# 2Filters.net
KiCad netlist of a schematic drawn in Altium Designer
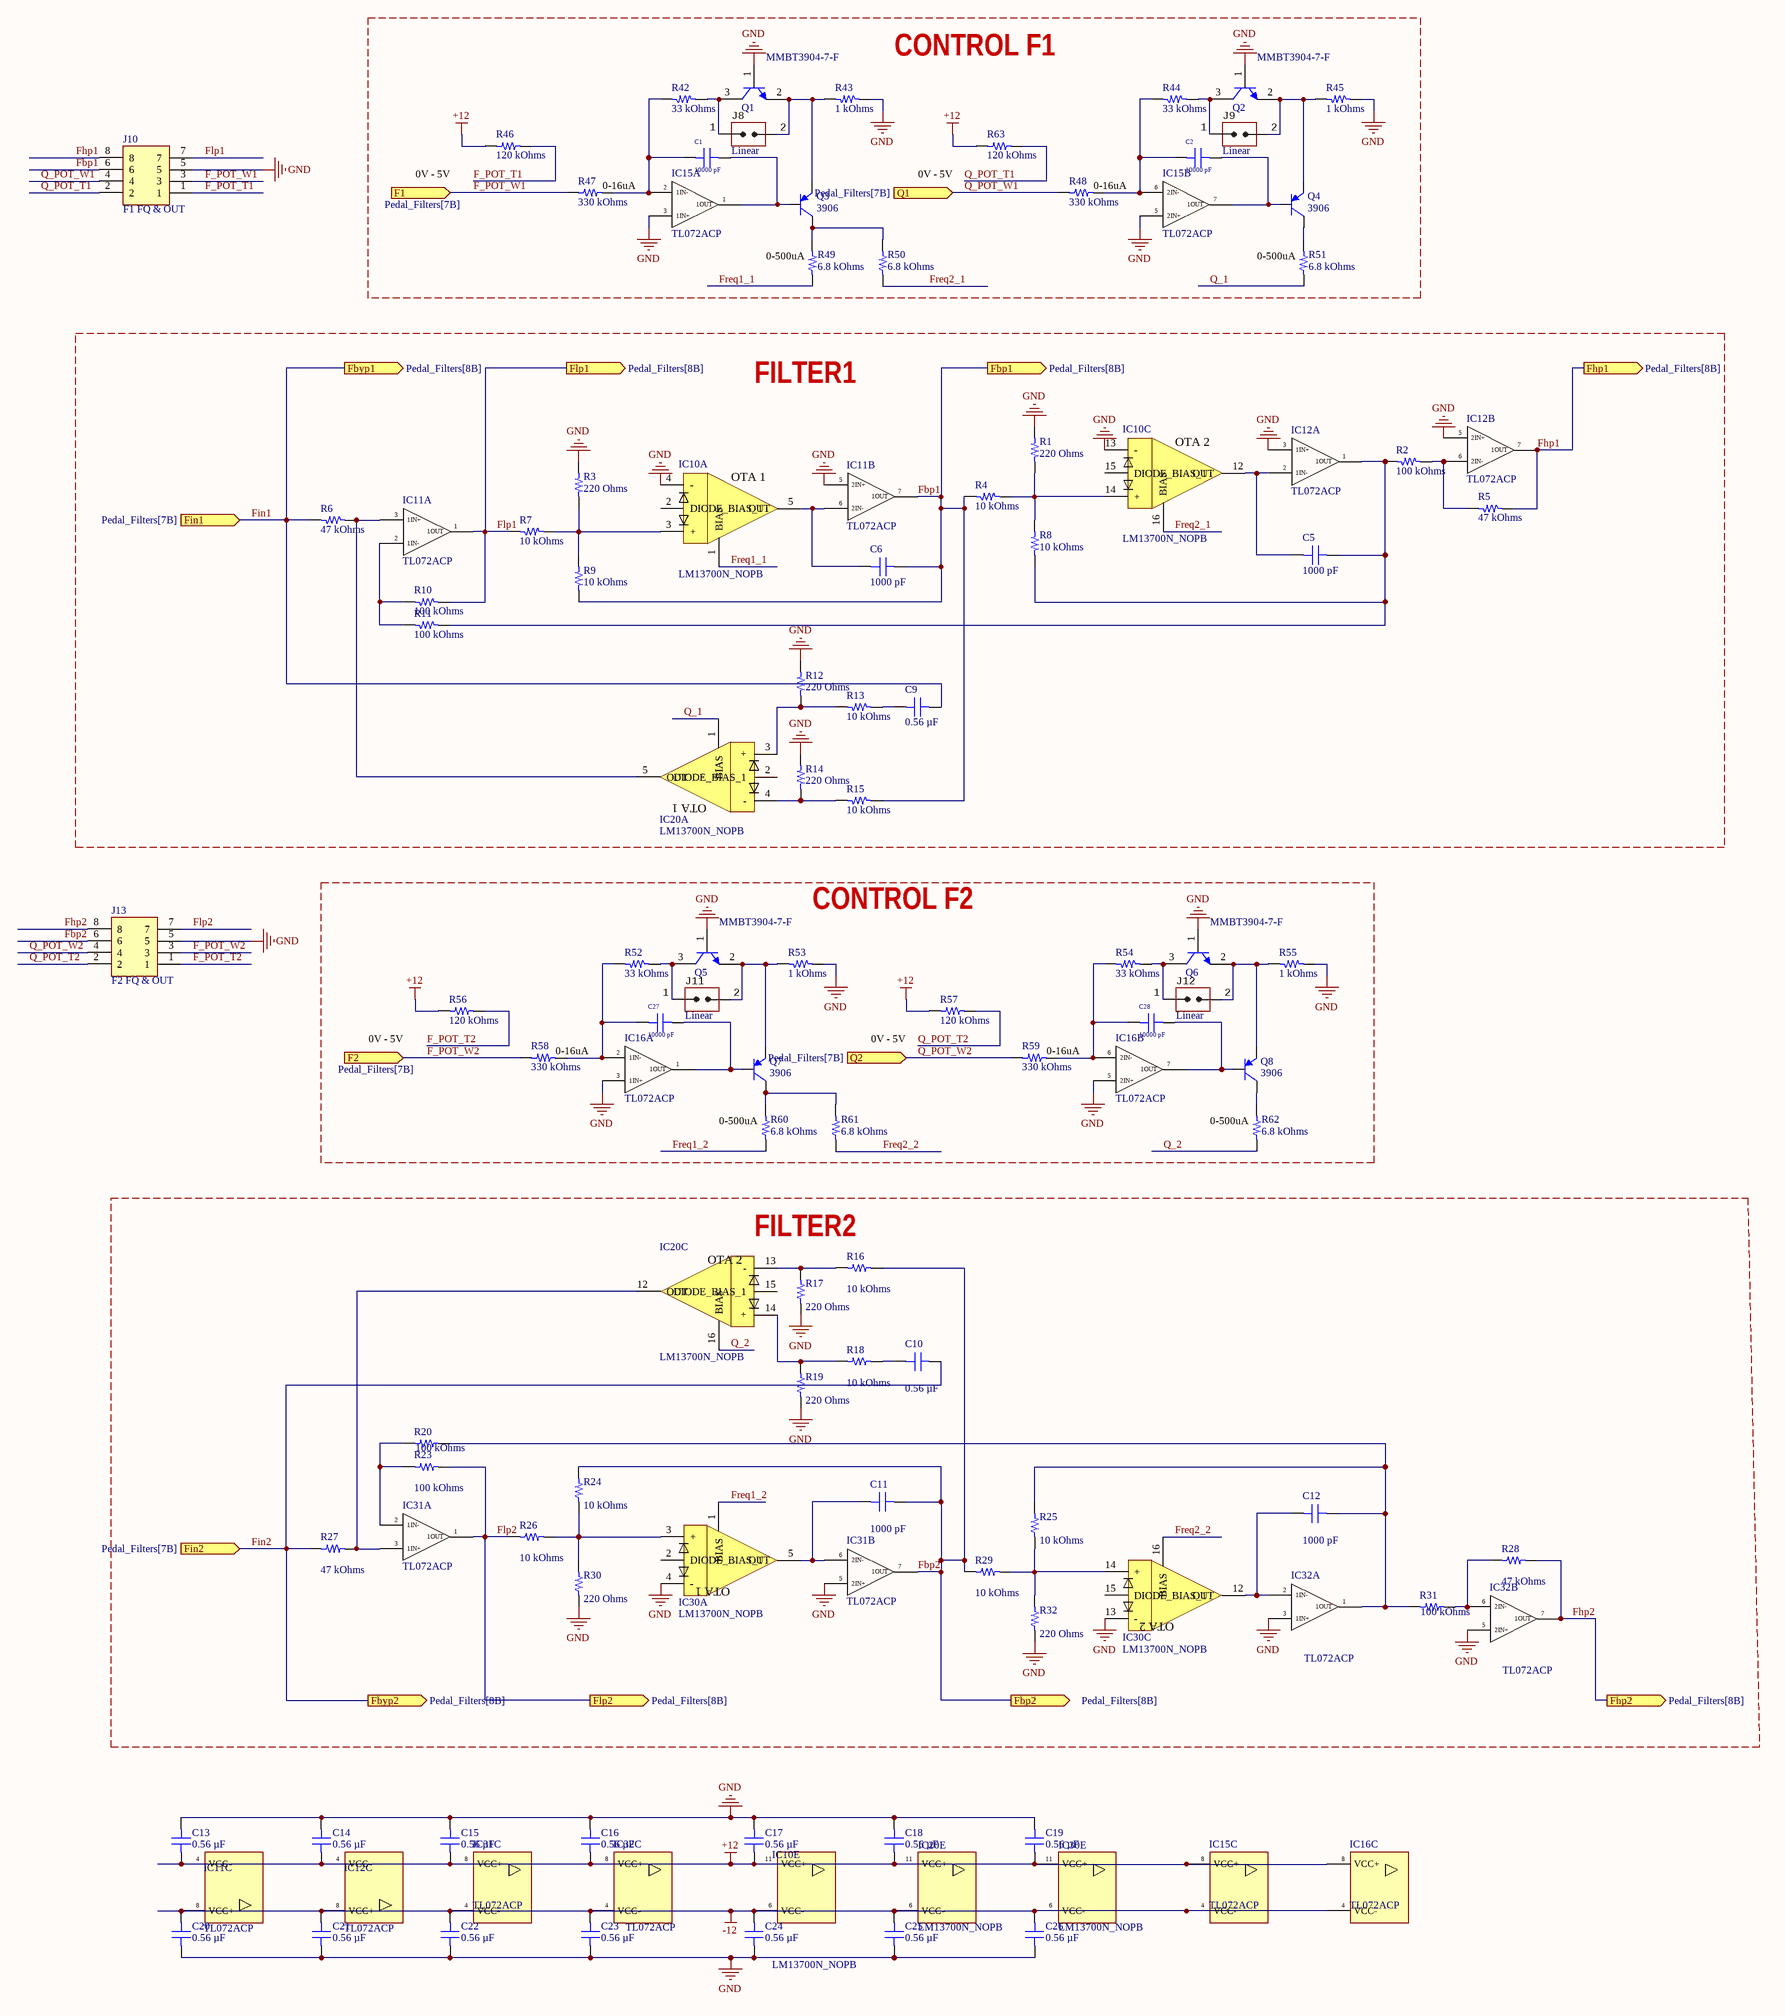
[diagram p0: 2Filters.SchDoc]

(export (version "E")
  (design (tool "Eeschema 10.0.6"))
  (components
    (comp (ref "C1")
      (value "10000 pF")
      (footprint "MURATA GRM188 0603_1608")
      (description "CAP CER 10000PF 50V C0G/NP0 0603")
      (fields
        (field (name "PART NUMBER") "GRM1885C1H103JA01D")
        (field (name "CAPACITANCE") "10000 pF")
        (field (name "MANUFACTURER") "Murata Electronics")
      )
      (libsource (lib "Celestial Altium Library - altium_library") (part "Capacitor"))
    )
    (comp (ref "C2")
      (value "10000 pF")
      (footprint "MURATA GRM188 0603_1608")
      (description "CAP CER 10000PF 50V C0G/NP0 0603")
      (fields
        (field (name "PART NUMBER") "GRM1885C1H103JA01D")
        (field (name "CAPACITANCE") "10000 pF")
        (field (name "MANUFACTURER") "Murata Electronics")
      )
      (libsource (lib "Celestial Altium Library - altium_library") (part "Capacitor"))
    )
    (comp (ref "C5")
      (value "~")
      (footprint "CAP 0805_2012")
      (description "CAP CER 0805 1NF 50V ULTRA STABL")
      (fields (field (name "PART NUMBER") "C0805X102J5HACAUTO") (field (name "CAPACITANCE") "1000 pF"))
      (libsource (lib "Celestial Altium Library - altium_library") (part "Capacitor"))
    )
    (comp (ref "C6")
      (value "~")
      (footprint "CAP 0805_2012")
      (description "CAP CER 0805 1NF 50V ULTRA STABL")
      (fields (field (name "PART NUMBER") "C0805X102J5HACAUTO") (field (name "CAPACITANCE") "1000 pF"))
      (libsource (lib "Celestial Altium Library - altium_library") (part "Capacitor"))
    )
    (comp (ref "C9")
      (value "~")
      (footprint "CAP 0805_2012")
      (description "CAP CER 0.56UF 50V X7R 0805")
      (fields (field (name "PART NUMBER") "C0805C564K5RAC7800") (field (name "CAPACITANCE") "0.56 µF"))
      (libsource (lib "Celestial Altium Library - altium_library") (part "Capacitor"))
    )
    (comp (ref "C10")
      (value "~")
      (footprint "CAP 0805_2012")
      (description "CAP CER 0.56UF 50V X7R 0805")
      (fields (field (name "PART NUMBER") "C0805C564K5RAC7800") (field (name "CAPACITANCE") "0.56 µF"))
      (libsource (lib "Celestial Altium Library - altium_library") (part "Capacitor"))
    )
    (comp (ref "C11")
      (value "~")
      (footprint "CAP 0805_2012")
      (description "CAP CER 0805 1NF 50V ULTRA STABL")
      (fields (field (name "PART NUMBER") "C0805X102J5HACAUTO") (field (name "CAPACITANCE") "1000 pF"))
      (libsource (lib "Celestial Altium Library - altium_library") (part "Capacitor"))
    )
    (comp (ref "C12")
      (value "~")
      (footprint "CAP 0805_2012")
      (description "CAP CER 0805 1NF 50V ULTRA STABL")
      (fields (field (name "PART NUMBER") "C0805X102J5HACAUTO") (field (name "CAPACITANCE") "1000 pF"))
      (libsource (lib "Celestial Altium Library - altium_library") (part "Capacitor"))
    )
    (comp (ref "C13")
      (value "~")
      (footprint "CAP 0805_2012")
      (description "CAP CER 0.56UF 50V X7R 0805")
      (fields (field (name "PART NUMBER") "C0805C564K5RAC7800") (field (name "CAPACITANCE") "0.56 µF"))
      (libsource (lib "Celestial Altium Library - altium_library") (part "Capacitor"))
    )
    (comp (ref "C14")
      (value "~")
      (footprint "CAP 0805_2012")
      (description "CAP CER 0.56UF 50V X7R 0805")
      (fields (field (name "PART NUMBER") "C0805C564K5RAC7800") (field (name "CAPACITANCE") "0.56 µF"))
      (libsource (lib "Celestial Altium Library - altium_library") (part "Capacitor"))
    )
    (comp (ref "C15")
      (value "~")
      (footprint "CAP 0805_2012")
      (description "CAP CER 0.56UF 50V X7R 0805")
      (fields (field (name "PART NUMBER") "C0805C564K5RAC7800") (field (name "CAPACITANCE") "0.56 µF"))
      (libsource (lib "Celestial Altium Library - altium_library") (part "Capacitor"))
    )
    (comp (ref "C16")
      (value "~")
      (footprint "CAP 0805_2012")
      (description "CAP CER 0.56UF 50V X7R 0805")
      (fields (field (name "PART NUMBER") "C0805C564K5RAC7800") (field (name "CAPACITANCE") "0.56 µF"))
      (libsource (lib "Celestial Altium Library - altium_library") (part "Capacitor"))
    )
    (comp (ref "C17")
      (value "~")
      (footprint "CAP 0805_2012")
      (description "CAP CER 0.56UF 50V X7R 0805")
      (fields (field (name "PART NUMBER") "C0805C564K5RAC7800") (field (name "CAPACITANCE") "0.56 µF"))
      (libsource (lib "Celestial Altium Library - altium_library") (part "Capacitor"))
    )
    (comp (ref "C18")
      (value "~")
      (footprint "CAP 0805_2012")
      (description "CAP CER 0.56UF 50V X7R 0805")
      (fields (field (name "PART NUMBER") "C0805C564K5RAC7800") (field (name "CAPACITANCE") "0.56 µF"))
      (libsource (lib "Celestial Altium Library - altium_library") (part "Capacitor"))
    )
    (comp (ref "C19")
      (value "~")
      (footprint "CAP 0805_2012")
      (description "CAP CER 0.56UF 50V X7R 0805")
      (fields (field (name "PART NUMBER") "C0805C564K5RAC7800") (field (name "CAPACITANCE") "0.56 µF"))
      (libsource (lib "Celestial Altium Library - altium_library") (part "Capacitor"))
    )
    (comp (ref "C20")
      (value "~")
      (footprint "CAP 0805_2012")
      (description "CAP CER 0.56UF 50V X7R 0805")
      (fields (field (name "PART NUMBER") "C0805C564K5RAC7800") (field (name "CAPACITANCE") "0.56 µF"))
      (libsource (lib "Celestial Altium Library - altium_library") (part "Capacitor"))
    )
    (comp (ref "C21")
      (value "~")
      (footprint "CAP 0805_2012")
      (description "CAP CER 0.56UF 50V X7R 0805")
      (fields (field (name "PART NUMBER") "C0805C564K5RAC7800") (field (name "CAPACITANCE") "0.56 µF"))
      (libsource (lib "Celestial Altium Library - altium_library") (part "Capacitor"))
    )
    (comp (ref "C22")
      (value "~")
      (footprint "CAP 0805_2012")
      (description "CAP CER 0.56UF 50V X7R 0805")
      (fields (field (name "PART NUMBER") "C0805C564K5RAC7800") (field (name "CAPACITANCE") "0.56 µF"))
      (libsource (lib "Celestial Altium Library - altium_library") (part "Capacitor"))
    )
    (comp (ref "C23")
      (value "~")
      (footprint "CAP 0805_2012")
      (description "CAP CER 0.56UF 50V X7R 0805")
      (fields (field (name "PART NUMBER") "C0805C564K5RAC7800") (field (name "CAPACITANCE") "0.56 µF"))
      (libsource (lib "Celestial Altium Library - altium_library") (part "Capacitor"))
    )
    (comp (ref "C24")
      (value "~")
      (footprint "CAP 0805_2012")
      (description "CAP CER 0.56UF 50V X7R 0805")
      (fields (field (name "PART NUMBER") "C0805C564K5RAC7800") (field (name "CAPACITANCE") "0.56 µF"))
      (libsource (lib "Celestial Altium Library - altium_library") (part "Capacitor"))
    )
    (comp (ref "C25")
      (value "~")
      (footprint "CAP 0805_2012")
      (description "CAP CER 0.56UF 50V X7R 0805")
      (fields (field (name "PART NUMBER") "C0805C564K5RAC7800") (field (name "CAPACITANCE") "0.56 µF"))
      (libsource (lib "Celestial Altium Library - altium_library") (part "Capacitor"))
    )
    (comp (ref "C26")
      (value "~")
      (footprint "CAP 0805_2012")
      (description "CAP CER 0.56UF 50V X7R 0805")
      (fields (field (name "PART NUMBER") "C0805C564K5RAC7800") (field (name "CAPACITANCE") "0.56 µF"))
      (libsource (lib "Celestial Altium Library - altium_library") (part "Capacitor"))
    )
    (comp (ref "C27")
      (value "10000 pF")
      (footprint "MURATA GRM188 0603_1608")
      (description "CAP CER 10000PF 50V C0G/NP0 0603")
      (fields
        (field (name "PART NUMBER") "GRM1885C1H103JA01D")
        (field (name "CAPACITANCE") "10000 pF")
        (field (name "MANUFACTURER") "Murata Electronics")
      )
      (libsource (lib "Celestial Altium Library - altium_library") (part "Capacitor"))
    )
    (comp (ref "C28")
      (value "10000 pF")
      (footprint "MURATA GRM188 0603_1608")
      (description "CAP CER 10000PF 50V C0G/NP0 0603")
      (fields
        (field (name "PART NUMBER") "GRM1885C1H103JA01D")
        (field (name "CAPACITANCE") "10000 pF")
        (field (name "MANUFACTURER") "Murata Electronics")
      )
      (libsource (lib "Celestial Altium Library - altium_library") (part "Capacitor"))
    )
    (comp (ref "IC10")
      (value "LM13700N_NOPB")
      (footprint "Analog:SOIC-16")
      (description "Integrated Circuit")
      (fields
        (field (name "MANUFACTURER_PART_NUMBER") "LM13700N/NOPB")
        (field (name "MOUSER PART NUMBER") "926-LM13700N/NOPB")
      )
      (libsource (lib "Analog") (part "LM13700N_NOPB"))
    )
    (comp (ref "IC11")
      (value "TL072ACP")
      (footprint "Analog:SOIC-8")
      (description "Integrated Circuit")
      (fields (field (name "MOUSER PART NUMBER") "595-TL072ACP"))
      (libsource (lib "") (part "TL072ACP_1"))
    )
    (comp (ref "IC12")
      (value "TL072ACP")
      (footprint "Analog:SOIC-8")
      (description "Integrated Circuit")
      (fields (field (name "MOUSER PART NUMBER") "595-TL072ACP"))
      (libsource (lib "") (part "TL072ACP_1"))
    )
    (comp (ref "IC15")
      (value "TL072ACP")
      (footprint "Analog:SOIC-8")
      (description "Integrated Circuit")
      (fields (field (name "MOUSER PART NUMBER") "595-TL072ACP"))
      (libsource (lib "Analog") (part "TL072ACP"))
    )
    (comp (ref "IC16")
      (value "TL072ACP")
      (footprint "Analog:SOIC-8")
      (description "Integrated Circuit")
      (fields (field (name "MOUSER PART NUMBER") "595-TL072ACP"))
      (libsource (lib "Analog") (part "TL072ACP"))
    )
    (comp (ref "IC20")
      (value "LM13700N_NOPB")
      (footprint "Analog:SOIC-16")
      (description "Integrated Circuit")
      (fields
        (field (name "MANUFACTURER_PART_NUMBER") "LM13700N/NOPB")
        (field (name "MOUSER PART NUMBER") "926-LM13700N/NOPB")
      )
      (libsource (lib "") (part "LM13700N_NOPB_3"))
    )
    (comp (ref "IC30")
      (value "LM13700N_NOPB")
      (footprint "Analog:SOIC-16")
      (description "Integrated Circuit")
      (fields
        (field (name "MANUFACTURER_PART_NUMBER") "LM13700N/NOPB")
        (field (name "MOUSER PART NUMBER") "926-LM13700N/NOPB")
      )
      (libsource (lib "") (part "LM13700N_NOPB_4"))
    )
    (comp (ref "IC31")
      (value "TL072ACP")
      (footprint "Analog:SOIC-8")
      (description "Integrated Circuit")
      (fields (field (name "MOUSER PART NUMBER") "595-TL072ACP"))
      (libsource (lib "Analog") (part "TL072ACP"))
    )
    (comp (ref "IC32")
      (value "TL072ACP")
      (footprint "Analog:SOIC-8")
      (description "Integrated Circuit")
      (fields (field (name "MOUSER PART NUMBER") "595-TL072ACP"))
      (libsource (lib "Analog") (part "TL072ACP"))
    )
    (comp (ref "J8")
      (value "Linear")
      (footprint "CON: JUMPER x1")
      (libsource (lib "connector") (part "Jumper_single"))
    )
    (comp (ref "J9")
      (value "Linear")
      (footprint "CON: JUMPER x1")
      (libsource (lib "connector") (part "Jumper_single"))
    )
    (comp (ref "J10")
      (value "F1 FQ & OUT")
      (footprint "LPPB042NFSSRC")
      (description "Connector")
      (fields (field (name "MANUFACTURER_PART_NUMBER") "LPPB042NFSS-RC"))
      (libsource (lib "SamacSys") (part "LPPB042NFSS-RC"))
    )
    (comp (ref "J11")
      (value "Linear")
      (footprint "CON: JUMPER x1")
      (libsource (lib "connector") (part "Jumper_single"))
    )
    (comp (ref "J12")
      (value "Linear")
      (footprint "CON: JUMPER x1")
      (libsource (lib "connector") (part "Jumper_single"))
    )
    (comp (ref "J13")
      (value "F2 FQ & OUT")
      (footprint "LPPB042NFSSRC")
      (description "Connector")
      (fields (field (name "MANUFACTURER_PART_NUMBER") "LPPB042NFSS-RC"))
      (libsource (lib "SamacSys") (part "LPPB042NFSS-RC"))
    )
    (comp (ref "Q1")
      (value "MMBT3904-7-F")
      (footprint "DIODES SOT-23-3")
      (description "TRANS NPN 40V 0.2A SOT23-3")
      (fields (field (name "MANUFACTURER") "Diodes Incorporated"))
      (libsource (lib "Celestial Altium Library - altium_library") (part "DIODES INC NPN SOT-23-3"))
    )
    (comp (ref "Q2")
      (value "MMBT3904-7-F")
      (footprint "DIODES SOT-23-3")
      (description "TRANS NPN 40V 0.2A SOT23-3")
      (fields (field (name "MANUFACTURER") "Diodes Incorporated"))
      (libsource (lib "Celestial Altium Library - altium_library") (part "DIODES INC NPN SOT-23-3"))
    )
    (comp (ref "Q3")
      (value "3906")
      (footprint "ProtoStack_H750VBT:SOT-23")
      (libsource (lib "ProtoStack_H750VBT") (part "MMBT3906"))
    )
    (comp (ref "Q4")
      (value "3906")
      (footprint "ProtoStack_H750VBT:SOT-23")
      (libsource (lib "ProtoStack_H750VBT") (part "MMBT3906"))
    )
    (comp (ref "Q5")
      (value "MMBT3904-7-F")
      (footprint "DIODES SOT-23-3")
      (description "TRANS NPN 40V 0.2A SOT23-3")
      (fields (field (name "MANUFACTURER") "Diodes Incorporated"))
      (libsource (lib "Celestial Altium Library - altium_library") (part "DIODES INC NPN SOT-23-3"))
    )
    (comp (ref "Q6")
      (value "MMBT3904-7-F")
      (footprint "DIODES SOT-23-3")
      (description "TRANS NPN 40V 0.2A SOT23-3")
      (fields (field (name "MANUFACTURER") "Diodes Incorporated"))
      (libsource (lib "Celestial Altium Library - altium_library") (part "DIODES INC NPN SOT-23-3"))
    )
    (comp (ref "Q7")
      (value "3906")
      (footprint "ProtoStack_H750VBT:SOT-23")
      (libsource (lib "ProtoStack_H750VBT") (part "MMBT3906"))
    )
    (comp (ref "Q8")
      (value "3906")
      (footprint "ProtoStack_H750VBT:SOT-23")
      (libsource (lib "ProtoStack_H750VBT") (part "MMBT3906"))
    )
    (comp (ref "R1")
      (value "220 Ohms")
      (footprint "RES 0603_1608")
      (description "RES SMD 220 OHM 1% 1/10W 0603")
      (fields (field (name "PART NUMBER") "CRCW0603220RFKEA"))
      (libsource (lib "Celestial Altium Library - altium_library") (part "Resistor"))
    )
    (comp (ref "R2")
      (value "100 kOhms")
      (footprint "RES 0603_1608")
      (description "RES SMD 100K OHM 1% 1/16W 0603")
      (fields (field (name "PART NUMBER") "CPF0603F100KC1"))
      (libsource (lib "Celestial Altium Library - altium_library") (part "Resistor"))
    )
    (comp (ref "R3")
      (value "220 Ohms")
      (footprint "RES 0603_1608")
      (description "RES SMD 220 OHM 1% 1/10W 0603")
      (fields (field (name "PART NUMBER") "CRCW0603220RFKEA"))
      (libsource (lib "Celestial Altium Library - altium_library") (part "Resistor"))
    )
    (comp (ref "R4")
      (value "10 kOhms")
      (footprint "RES 0603_1608")
      (description "RES SMD 10K OHM 1% 1/10W 0603")
      (fields (field (name "PART NUMBER") "CRCW060310K0FKEA"))
      (libsource (lib "Celestial Altium Library - altium_library") (part "Resistor"))
    )
    (comp (ref "R5")
      (value "47 kOhms")
      (footprint "RES 0603_1608")
      (description "RES SMD 47K OHM 1% 1/3W 0603")
      (fields (field (name "PART NUMBER") "CRCW060347K0FKEAHP"))
      (libsource (lib "Celestial Altium Library - altium_library") (part "Resistor"))
    )
    (comp (ref "R6")
      (value "47 kOhms")
      (footprint "RES 0603_1608")
      (description "RES SMD 47K OHM 1% 1/3W 0603")
      (fields (field (name "PART NUMBER") "CRCW060347K0FKEAHP"))
      (libsource (lib "Celestial Altium Library - altium_library") (part "Resistor"))
    )
    (comp (ref "R7")
      (value "10 kOhms")
      (footprint "RES 0603_1608")
      (description "RES SMD 10K OHM 1% 1/10W 0603")
      (fields (field (name "PART NUMBER") "CRCW060310K0FKEA"))
      (libsource (lib "Celestial Altium Library - altium_library") (part "Resistor"))
    )
    (comp (ref "R8")
      (value "10 kOhms")
      (footprint "RES 0603_1608")
      (description "RES SMD 10K OHM 1% 1/10W 0603")
      (fields (field (name "PART NUMBER") "CRCW060310K0FKEA"))
      (libsource (lib "Celestial Altium Library - altium_library") (part "Resistor"))
    )
    (comp (ref "R9")
      (value "10 kOhms")
      (footprint "RES 0603_1608")
      (description "RES SMD 10K OHM 1% 1/10W 0603")
      (fields (field (name "PART NUMBER") "CRCW060310K0FKEA"))
      (libsource (lib "Celestial Altium Library - altium_library") (part "Resistor"))
    )
    (comp (ref "R10")
      (value "100 kOhms")
      (footprint "RES 0603_1608")
      (description "RES SMD 100K OHM 1% 1/16W 0603")
      (fields (field (name "PART NUMBER") "CPF0603F100KC1"))
      (libsource (lib "Celestial Altium Library - altium_library") (part "Resistor"))
    )
    (comp (ref "R11")
      (value "100 kOhms")
      (footprint "RES 0603_1608")
      (description "RES SMD 100K OHM 1% 1/16W 0603")
      (fields (field (name "PART NUMBER") "CPF0603F100KC1"))
      (libsource (lib "Celestial Altium Library - altium_library") (part "Resistor"))
    )
    (comp (ref "R12")
      (value "220 Ohms")
      (footprint "RES 0603_1608")
      (description "RES SMD 220 OHM 1% 1/10W 0603")
      (fields (field (name "PART NUMBER") "CRCW0603220RFKEA"))
      (libsource (lib "Celestial Altium Library - altium_library") (part "Resistor"))
    )
    (comp (ref "R13")
      (value "10 kOhms")
      (footprint "RES 0603_1608")
      (description "RES SMD 10K OHM 1% 1/10W 0603")
      (fields (field (name "PART NUMBER") "CRCW060310K0FKEA"))
      (libsource (lib "Celestial Altium Library - altium_library") (part "Resistor"))
    )
    (comp (ref "R14")
      (value "220 Ohms")
      (footprint "RES 0603_1608")
      (description "RES SMD 220 OHM 1% 1/10W 0603")
      (fields (field (name "PART NUMBER") "CRCW0603220RFKEA"))
      (libsource (lib "Celestial Altium Library - altium_library") (part "Resistor"))
    )
    (comp (ref "R15")
      (value "10 kOhms")
      (footprint "RES 0603_1608")
      (description "RES SMD 10K OHM 1% 1/10W 0603")
      (fields (field (name "PART NUMBER") "CRCW060310K0FKEA"))
      (libsource (lib "Celestial Altium Library - altium_library") (part "Resistor"))
    )
    (comp (ref "R16")
      (value "10 kOhms")
      (footprint "RES 0603_1608")
      (description "RES SMD 10K OHM 1% 1/10W 0603")
      (fields (field (name "PART NUMBER") "CRCW060310K0FKEA"))
      (libsource (lib "Celestial Altium Library - altium_library") (part "Resistor"))
    )
    (comp (ref "R17")
      (value "220 Ohms")
      (footprint "RES 0603_1608")
      (description "RES SMD 220 OHM 1% 1/10W 0603")
      (fields (field (name "PART NUMBER") "CRCW0603220RFKEA"))
      (libsource (lib "Celestial Altium Library - altium_library") (part "Resistor"))
    )
    (comp (ref "R18")
      (value "10 kOhms")
      (footprint "RES 0603_1608")
      (description "RES SMD 10K OHM 1% 1/10W 0603")
      (fields (field (name "PART NUMBER") "CRCW060310K0FKEA"))
      (libsource (lib "Celestial Altium Library - altium_library") (part "Resistor"))
    )
    (comp (ref "R19")
      (value "220 Ohms")
      (footprint "RES 0603_1608")
      (description "RES SMD 220 OHM 1% 1/10W 0603")
      (fields (field (name "PART NUMBER") "CRCW0603220RFKEA"))
      (libsource (lib "Celestial Altium Library - altium_library") (part "Resistor"))
    )
    (comp (ref "R20")
      (value "100 kOhms")
      (footprint "RES 0603_1608")
      (description "RES SMD 100K OHM 1% 1/16W 0603")
      (fields (field (name "PART NUMBER") "CPF0603F100KC1"))
      (libsource (lib "Celestial Altium Library - altium_library") (part "Resistor"))
    )
    (comp (ref "R23")
      (value "100 kOhms")
      (footprint "RES 0603_1608")
      (description "RES SMD 100K OHM 1% 1/16W 0603")
      (fields (field (name "PART NUMBER") "CPF0603F100KC1"))
      (libsource (lib "Celestial Altium Library - altium_library") (part "Resistor"))
    )
    (comp (ref "R24")
      (value "10 kOhms")
      (footprint "RES 0603_1608")
      (description "RES SMD 10K OHM 1% 1/10W 0603")
      (fields (field (name "PART NUMBER") "CRCW060310K0FKEA"))
      (libsource (lib "Celestial Altium Library - altium_library") (part "Resistor"))
    )
    (comp (ref "R25")
      (value "10 kOhms")
      (footprint "RES 0603_1608")
      (description "RES SMD 10K OHM 1% 1/10W 0603")
      (fields (field (name "PART NUMBER") "CRCW060310K0FKEA"))
      (libsource (lib "Celestial Altium Library - altium_library") (part "Resistor"))
    )
    (comp (ref "R26")
      (value "10 kOhms")
      (footprint "RES 0603_1608")
      (description "RES SMD 10K OHM 1% 1/10W 0603")
      (fields (field (name "PART NUMBER") "CRCW060310K0FKEA"))
      (libsource (lib "Celestial Altium Library - altium_library") (part "Resistor"))
    )
    (comp (ref "R27")
      (value "47 kOhms")
      (footprint "RES 0603_1608")
      (description "RES SMD 47K OHM 1% 1/3W 0603")
      (fields (field (name "PART NUMBER") "CRCW060347K0FKEAHP"))
      (libsource (lib "Celestial Altium Library - altium_library") (part "Resistor"))
    )
    (comp (ref "R28")
      (value "47 kOhms")
      (footprint "RES 0603_1608")
      (description "RES SMD 47K OHM 1% 1/3W 0603")
      (fields (field (name "PART NUMBER") "CRCW060347K0FKEAHP"))
      (libsource (lib "Celestial Altium Library - altium_library") (part "Resistor"))
    )
    (comp (ref "R29")
      (value "10 kOhms")
      (footprint "RES 0603_1608")
      (description "RES SMD 10K OHM 1% 1/10W 0603")
      (fields (field (name "PART NUMBER") "CRCW060310K0FKEA"))
      (libsource (lib "Celestial Altium Library - altium_library") (part "Resistor"))
    )
    (comp (ref "R30")
      (value "220 Ohms")
      (footprint "RES 0603_1608")
      (description "RES SMD 220 OHM 1% 1/10W 0603")
      (fields (field (name "PART NUMBER") "CRCW0603220RFKEA"))
      (libsource (lib "Celestial Altium Library - altium_library") (part "Resistor"))
    )
    (comp (ref "R31")
      (value "100 kOhms")
      (footprint "RES 0603_1608")
      (description "RES SMD 100K OHM 1% 1/16W 0603")
      (fields (field (name "PART NUMBER") "CPF0603F100KC1"))
      (libsource (lib "Celestial Altium Library - altium_library") (part "Resistor"))
    )
    (comp (ref "R32")
      (value "220 Ohms")
      (footprint "RES 0603_1608")
      (description "RES SMD 220 OHM 1% 1/10W 0603")
      (fields (field (name "PART NUMBER") "CRCW0603220RFKEA"))
      (libsource (lib "Celestial Altium Library - altium_library") (part "Resistor"))
    )
    (comp (ref "R42")
      (value "33 kOhms")
      (footprint "YAGEO RES 0603_1608")
      (description "RES SMD 33K OHM 1% 1/10W 0603")
      (fields (field (name "PART NUMBER") "AC0603FR-0733KL") (field (name "MANUFACTURER") "Yageo"))
      (libsource (lib "Celestial Altium Library - altium_library") (part "Resistor"))
    )
    (comp (ref "R43")
      (value "1 kOhms")
      (footprint "YAGEO RES 0603_1608")
      (description "RES SMD 1K OHM 1% 1/10W 0603")
      (fields (field (name "PART NUMBER") "AA0603FR-071KL") (field (name "MANUFACTURER") "Yageo"))
      (libsource (lib "Celestial Altium Library - altium_library") (part "Resistor"))
    )
    (comp (ref "R44")
      (value "33 kOhms")
      (footprint "YAGEO RES 0603_1608")
      (description "RES SMD 33K OHM 1% 1/10W 0603")
      (fields (field (name "PART NUMBER") "AC0603FR-0733KL") (field (name "MANUFACTURER") "Yageo"))
      (libsource (lib "Celestial Altium Library - altium_library") (part "Resistor"))
    )
    (comp (ref "R45")
      (value "1 kOhms")
      (footprint "YAGEO RES 0603_1608")
      (description "RES SMD 1K OHM 1% 1/10W 0603")
      (fields (field (name "PART NUMBER") "AA0603FR-071KL") (field (name "MANUFACTURER") "Yageo"))
      (libsource (lib "Celestial Altium Library - altium_library") (part "Resistor"))
    )
    (comp (ref "R46")
      (value "120 kOhms")
      (footprint "YAGEO RES 0603_1608")
      (description "RES SMD 120K OHM 1% 1/10W 0603")
      (fields (field (name "PART NUMBER") "AC0603FR-07120KL") (field (name "MANUFACTURER") "Yageo"))
      (libsource (lib "Celestial Altium Library - altium_library") (part "Resistor"))
    )
    (comp (ref "R47")
      (value "330 kOhms")
      (footprint "YAGEO RES 0603_1608")
      (description "RES SMD 330K OHM 1% 1/10W 0603")
      (fields (field (name "PART NUMBER") "AC0603FR-07330KL") (field (name "MANUFACTURER") "Yageo"))
      (libsource (lib "Celestial Altium Library - altium_library") (part "Resistor"))
    )
    (comp (ref "R48")
      (value "330 kOhms")
      (footprint "YAGEO RES 0603_1608")
      (description "RES SMD 330K OHM 1% 1/10W 0603")
      (fields (field (name "PART NUMBER") "AC0603FR-07330KL") (field (name "MANUFACTURER") "Yageo"))
      (libsource (lib "Celestial Altium Library - altium_library") (part "Resistor"))
    )
    (comp (ref "R49")
      (value "6.8 kOhms")
      (footprint "YAGEO RES 0603_1608")
      (description "RES SMD 6.8K OHM 1% 1/10W 0603")
      (fields (field (name "PART NUMBER") "AC0603FR-076K8L") (field (name "MANUFACTURER") "Yageo"))
      (libsource (lib "Celestial Altium Library - altium_library") (part "Resistor"))
    )
    (comp (ref "R50")
      (value "6.8 kOhms")
      (footprint "YAGEO RES 0603_1608")
      (description "RES SMD 6.8K OHM 1% 1/10W 0603")
      (fields (field (name "PART NUMBER") "AC0603FR-076K8L") (field (name "MANUFACTURER") "Yageo"))
      (libsource (lib "Celestial Altium Library - altium_library") (part "Resistor"))
    )
    (comp (ref "R51")
      (value "6.8 kOhms")
      (footprint "YAGEO RES 0603_1608")
      (description "RES SMD 6.8K OHM 1% 1/10W 0603")
      (fields (field (name "PART NUMBER") "AC0603FR-076K8L") (field (name "MANUFACTURER") "Yageo"))
      (libsource (lib "Celestial Altium Library - altium_library") (part "Resistor"))
    )
    (comp (ref "R52")
      (value "33 kOhms")
      (footprint "YAGEO RES 0603_1608")
      (description "RES SMD 33K OHM 1% 1/10W 0603")
      (fields (field (name "PART NUMBER") "AC0603FR-0733KL") (field (name "MANUFACTURER") "Yageo"))
      (libsource (lib "Celestial Altium Library - altium_library") (part "Resistor"))
    )
    (comp (ref "R53")
      (value "1 kOhms")
      (footprint "YAGEO RES 0603_1608")
      (description "RES SMD 1K OHM 1% 1/10W 0603")
      (fields (field (name "PART NUMBER") "AA0603FR-071KL") (field (name "MANUFACTURER") "Yageo"))
      (libsource (lib "Celestial Altium Library - altium_library") (part "Resistor"))
    )
    (comp (ref "R54")
      (value "33 kOhms")
      (footprint "YAGEO RES 0603_1608")
      (description "RES SMD 33K OHM 1% 1/10W 0603")
      (fields (field (name "PART NUMBER") "AC0603FR-0733KL") (field (name "MANUFACTURER") "Yageo"))
      (libsource (lib "Celestial Altium Library - altium_library") (part "Resistor"))
    )
    (comp (ref "R55")
      (value "1 kOhms")
      (footprint "YAGEO RES 0603_1608")
      (description "RES SMD 1K OHM 1% 1/10W 0603")
      (fields (field (name "PART NUMBER") "AA0603FR-071KL") (field (name "MANUFACTURER") "Yageo"))
      (libsource (lib "Celestial Altium Library - altium_library") (part "Resistor"))
    )
    (comp (ref "R56")
      (value "120 kOhms")
      (footprint "YAGEO RES 0603_1608")
      (description "RES SMD 120K OHM 1% 1/10W 0603")
      (fields (field (name "PART NUMBER") "AC0603FR-07120KL") (field (name "MANUFACTURER") "Yageo"))
      (libsource (lib "Celestial Altium Library - altium_library") (part "Resistor"))
    )
    (comp (ref "R57")
      (value "120 kOhms")
      (footprint "YAGEO RES 0603_1608")
      (description "RES SMD 120K OHM 1% 1/10W 0603")
      (fields (field (name "PART NUMBER") "AC0603FR-07120KL") (field (name "MANUFACTURER") "Yageo"))
      (libsource (lib "Celestial Altium Library - altium_library") (part "Resistor"))
    )
    (comp (ref "R58")
      (value "330 kOhms")
      (footprint "YAGEO RES 0603_1608")
      (description "RES SMD 330K OHM 1% 1/10W 0603")
      (fields (field (name "PART NUMBER") "AC0603FR-07330KL") (field (name "MANUFACTURER") "Yageo"))
      (libsource (lib "Celestial Altium Library - altium_library") (part "Resistor"))
    )
    (comp (ref "R59")
      (value "330 kOhms")
      (footprint "YAGEO RES 0603_1608")
      (description "RES SMD 330K OHM 1% 1/10W 0603")
      (fields (field (name "PART NUMBER") "AC0603FR-07330KL") (field (name "MANUFACTURER") "Yageo"))
      (libsource (lib "Celestial Altium Library - altium_library") (part "Resistor"))
    )
    (comp (ref "R60")
      (value "6.8 kOhms")
      (footprint "YAGEO RES 0603_1608")
      (description "RES SMD 6.8K OHM 1% 1/10W 0603")
      (fields (field (name "PART NUMBER") "AC0603FR-076K8L") (field (name "MANUFACTURER") "Yageo"))
      (libsource (lib "Celestial Altium Library - altium_library") (part "Resistor"))
    )
    (comp (ref "R61")
      (value "6.8 kOhms")
      (footprint "YAGEO RES 0603_1608")
      (description "RES SMD 6.8K OHM 1% 1/10W 0603")
      (fields (field (name "PART NUMBER") "AC0603FR-076K8L") (field (name "MANUFACTURER") "Yageo"))
      (libsource (lib "Celestial Altium Library - altium_library") (part "Resistor"))
    )
    (comp (ref "R62")
      (value "6.8 kOhms")
      (footprint "YAGEO RES 0603_1608")
      (description "RES SMD 6.8K OHM 1% 1/10W 0603")
      (fields (field (name "PART NUMBER") "AC0603FR-076K8L") (field (name "MANUFACTURER") "Yageo"))
      (libsource (lib "Celestial Altium Library - altium_library") (part "Resistor"))
    )
    (comp (ref "R63")
      (value "120 kOhms")
      (footprint "YAGEO RES 0603_1608")
      (description "RES SMD 120K OHM 1% 1/10W 0603")
      (fields (field (name "PART NUMBER") "AC0603FR-07120KL") (field (name "MANUFACTURER") "Yageo"))
      (libsource (lib "Celestial Altium Library - altium_library") (part "Resistor"))
    )
  )
  (nets
    (net (code "1") (name "+12") (class "Default")
      (node (ref "C13") (pin "1") (pinfunction "1_1") (pintype "passive"))
      (node (ref "C14") (pin "1") (pinfunction "1_1") (pintype "passive"))
      (node (ref "C15") (pin "1") (pinfunction "1_1") (pintype "passive"))
      (node (ref "C16") (pin "1") (pinfunction "1_1") (pintype "passive"))
      (node (ref "C17") (pin "1") (pinfunction "1_1") (pintype "passive"))
      (node (ref "C18") (pin "1") (pinfunction "1_1") (pintype "passive"))
      (node (ref "C19") (pin "1") (pinfunction "1_1") (pintype "passive"))
      (node (ref "IC10") (pin "11") (pinfunction "VCC+_11") (pintype "passive"))
      (node (ref "IC11") (pin "4") (pinfunction "VCC-_4") (pintype "passive"))
      (node (ref "IC12") (pin "4") (pinfunction "VCC-_4") (pintype "passive"))
      (node (ref "IC15") (pin "8") (pinfunction "VCC+_8") (pintype "passive"))
      (node (ref "IC16") (pin "8") (pinfunction "VCC+_8") (pintype "passive"))
      (node (ref "IC20") (pin "11") (pinfunction "VCC+_11") (pintype "passive"))
      (node (ref "IC30") (pin "11") (pinfunction "VCC+_11") (pintype "passive"))
      (node (ref "IC31") (pin "8") (pinfunction "VCC+_8") (pintype "passive"))
      (node (ref "IC32") (pin "8") (pinfunction "VCC+_8") (pintype "passive"))
      (node (ref "R46") (pin "1") (pinfunction "1_1") (pintype "passive"))
      (node (ref "R56") (pin "1") (pinfunction "1_1") (pintype "passive"))
      (node (ref "R57") (pin "1") (pinfunction "1_1") (pintype "passive"))
      (node (ref "R63") (pin "1") (pinfunction "1_1") (pintype "passive"))
    )
    (net (code "2") (name "-12") (class "Default")
      (node (ref "C20") (pin "2") (pinfunction "2_2") (pintype "passive"))
      (node (ref "C21") (pin "2") (pinfunction "2_2") (pintype "passive"))
      (node (ref "C22") (pin "2") (pinfunction "2_2") (pintype "passive"))
      (node (ref "C23") (pin "2") (pinfunction "2_2") (pintype "passive"))
      (node (ref "C24") (pin "2") (pinfunction "2_2") (pintype "passive"))
      (node (ref "C25") (pin "2") (pinfunction "2_2") (pintype "passive"))
      (node (ref "C26") (pin "2") (pinfunction "2_2") (pintype "passive"))
      (node (ref "IC10") (pin "6") (pinfunction "VCC-_6") (pintype "passive"))
      (node (ref "IC11") (pin "8") (pinfunction "VCC+_8") (pintype "passive"))
      (node (ref "IC12") (pin "8") (pinfunction "VCC+_8") (pintype "passive"))
      (node (ref "IC15") (pin "4") (pinfunction "VCC-_4") (pintype "passive"))
      (node (ref "IC16") (pin "4") (pinfunction "VCC-_4") (pintype "passive"))
      (node (ref "IC20") (pin "6") (pinfunction "VCC-_6") (pintype "passive"))
      (node (ref "IC30") (pin "6") (pinfunction "VCC-_6") (pintype "passive"))
      (node (ref "IC31") (pin "4") (pinfunction "VCC-_4") (pintype "passive"))
      (node (ref "IC32") (pin "4") (pinfunction "VCC-_4") (pintype "passive"))
    )
    (net (code "3") (name "/F_POT_T1") (class "Default")
      (node (ref "J10") (pin "1") (pinfunction "1_1") (pintype "passive"))
      (node (ref "R46") (pin "2") (pinfunction "2_2") (pintype "passive"))
    )
    (net (code "4") (name "/F_POT_T2") (class "Default")
      (node (ref "J13") (pin "1") (pinfunction "1_1") (pintype "passive"))
      (node (ref "R56") (pin "2") (pinfunction "2_2") (pintype "passive"))
    )
    (net (code "5") (name "/F_POT_W1") (class "Default")
      (node (ref "J10") (pin "3") (pinfunction "3_3") (pintype "passive"))
      (node (ref "R47") (pin "1") (pinfunction "1_1") (pintype "passive"))
    )
    (net (code "6") (name "/F_POT_W2") (class "Default")
      (node (ref "J13") (pin "3") (pinfunction "3_3") (pintype "passive"))
      (node (ref "R58") (pin "1") (pinfunction "1_1") (pintype "passive"))
    )
    (net (code "7") (name "/Fbp1") (class "Default")
      (node (ref "C6") (pin "1") (pinfunction "1_1") (pintype "passive"))
      (node (ref "IC11") (pin "7") (pinfunction "1OUT_7") (pintype "passive"))
      (node (ref "J10") (pin "6") (pinfunction "6_6") (pintype "passive"))
      (node (ref "R15") (pin "2") (pinfunction "2_2") (pintype "passive"))
      (node (ref "R4") (pin "1") (pinfunction "1_1") (pintype "passive"))
      (node (ref "R9") (pin "2") (pinfunction "2_2") (pintype "passive"))
    )
    (net (code "8") (name "/Fbp2") (class "Default")
      (node (ref "C11") (pin "1") (pinfunction "1_1") (pintype "passive"))
      (node (ref "IC31") (pin "7") (pinfunction "1OUT_7") (pintype "passive"))
      (node (ref "J13") (pin "6") (pinfunction "6_6") (pintype "passive"))
      (node (ref "R16") (pin "2") (pinfunction "2_2") (pintype "passive"))
      (node (ref "R24") (pin "2") (pinfunction "2_2") (pintype "passive"))
      (node (ref "R29") (pin "1") (pinfunction "1_1") (pintype "passive"))
    )
    (net (code "9") (name "/Fhp1") (class "Default")
      (node (ref "IC12") (pin "7") (pinfunction "1OUT_7") (pintype "passive"))
      (node (ref "J10") (pin "8") (pinfunction "8_8") (pintype "passive"))
      (node (ref "R5") (pin "2") (pinfunction "2_2") (pintype "passive"))
    )
    (net (code "10") (name "/Fhp2") (class "Default")
      (node (ref "IC32") (pin "7") (pinfunction "1OUT_7") (pintype "passive"))
      (node (ref "J13") (pin "8") (pinfunction "8_8") (pintype "passive"))
      (node (ref "R28") (pin "2") (pinfunction "2_2") (pintype "passive"))
    )
    (net (code "11") (name "/Fin1") (class "Default")
      (node (ref "C9") (pin "2") (pinfunction "2_2") (pintype "passive"))
      (node (ref "R6") (pin "1") (pinfunction "1_1") (pintype "passive"))
    )
    (net (code "12") (name "/Fin2") (class "Default")
      (node (ref "C10") (pin "2") (pinfunction "2_2") (pintype "passive"))
      (node (ref "R27") (pin "1") (pinfunction "1_1") (pintype "passive"))
    )
    (net (code "13") (name "/Flp1") (class "Default")
      (node (ref "IC11") (pin "1") (pinfunction "1OUT_1") (pintype "passive"))
      (node (ref "J10") (pin "7") (pinfunction "7_7") (pintype "passive"))
      (node (ref "R10") (pin "2") (pinfunction "2_2") (pintype "passive"))
      (node (ref "R7") (pin "1") (pinfunction "1_1") (pintype "passive"))
    )
    (net (code "14") (name "/Flp2") (class "Default")
      (node (ref "IC31") (pin "1") (pinfunction "1OUT_1") (pintype "passive"))
      (node (ref "J13") (pin "7") (pinfunction "7_7") (pintype "passive"))
      (node (ref "R23") (pin "2") (pinfunction "2_2") (pintype "passive"))
      (node (ref "R26") (pin "1") (pinfunction "1_1") (pintype "passive"))
    )
    (net (code "15") (name "/Freq1_1") (class "Default")
      (node (ref "IC10") (pin "1") (pinfunction "BIAS_1") (pintype "passive"))
      (node (ref "R49") (pin "1") (pinfunction "1_1") (pintype "passive"))
    )
    (net (code "16") (name "/Freq1_2") (class "Default")
      (node (ref "IC30") (pin "1") (pinfunction "BIAS_1") (pintype "passive"))
      (node (ref "R60") (pin "1") (pinfunction "1_1") (pintype "passive"))
    )
    (net (code "17") (name "/Freq2_1") (class "Default")
      (node (ref "IC10") (pin "16") (pinfunction "BIAS_16") (pintype "passive"))
      (node (ref "R50") (pin "1") (pinfunction "1_1") (pintype "passive"))
    )
    (net (code "18") (name "/Freq2_2") (class "Default")
      (node (ref "IC30") (pin "16") (pinfunction "BIAS_16") (pintype "passive"))
      (node (ref "R61") (pin "1") (pinfunction "1_1") (pintype "passive"))
    )
    (net (code "19") (name "/Q_1") (class "Default")
      (node (ref "IC20") (pin "1") (pinfunction "BIAS_1") (pintype "passive"))
      (node (ref "R51") (pin "1") (pinfunction "1_1") (pintype "passive"))
    )
    (net (code "20") (name "/Q_2") (class "Default")
      (node (ref "IC20") (pin "16") (pinfunction "BIAS_16") (pintype "passive"))
      (node (ref "R62") (pin "1") (pinfunction "1_1") (pintype "passive"))
    )
    (net (code "21") (name "/Q_POT_T1") (class "Default")
      (node (ref "J10") (pin "2") (pinfunction "2_2") (pintype "passive"))
      (node (ref "R63") (pin "2") (pinfunction "2_2") (pintype "passive"))
    )
    (net (code "22") (name "/Q_POT_T2") (class "Default")
      (node (ref "J13") (pin "2") (pinfunction "2_2") (pintype "passive"))
      (node (ref "R57") (pin "2") (pinfunction "2_2") (pintype "passive"))
    )
    (net (code "23") (name "/Q_POT_W1") (class "Default")
      (node (ref "J10") (pin "4") (pinfunction "4_4") (pintype "passive"))
      (node (ref "R48") (pin "1") (pinfunction "1_1") (pintype "passive"))
    )
    (net (code "24") (name "/Q_POT_W2") (class "Default")
      (node (ref "J13") (pin "4") (pinfunction "4_4") (pintype "passive"))
      (node (ref "R59") (pin "1") (pinfunction "1_1") (pintype "passive"))
    )
    (net (code "25") (name "GND") (class "Default")
      (node (ref "C13") (pin "2") (pinfunction "2_2") (pintype "passive"))
      (node (ref "C14") (pin "2") (pinfunction "2_2") (pintype "passive"))
      (node (ref "C15") (pin "2") (pinfunction "2_2") (pintype "passive"))
      (node (ref "C16") (pin "2") (pinfunction "2_2") (pintype "passive"))
      (node (ref "C17") (pin "2") (pinfunction "2_2") (pintype "passive"))
      (node (ref "C18") (pin "2") (pinfunction "2_2") (pintype "passive"))
      (node (ref "C19") (pin "2") (pinfunction "2_2") (pintype "passive"))
      (node (ref "C20") (pin "1") (pinfunction "1_1") (pintype "passive"))
      (node (ref "C21") (pin "1") (pinfunction "1_1") (pintype "passive"))
      (node (ref "C22") (pin "1") (pinfunction "1_1") (pintype "passive"))
      (node (ref "C23") (pin "1") (pinfunction "1_1") (pintype "passive"))
      (node (ref "C24") (pin "1") (pinfunction "1_1") (pintype "passive"))
      (node (ref "C25") (pin "1") (pinfunction "1_1") (pintype "passive"))
      (node (ref "C26") (pin "1") (pinfunction "1_1") (pintype "passive"))
      (node (ref "IC10") (pin "13") (pinfunction "-_13") (pintype "passive"))
      (node (ref "IC10") (pin "4") (pinfunction "-_4") (pintype "passive"))
      (node (ref "IC11") (pin "5") (pinfunction "2IN+_5") (pintype "passive"))
      (node (ref "IC12") (pin "3") (pinfunction "1IN+_3") (pintype "passive"))
      (node (ref "IC12") (pin "5") (pinfunction "2IN+_5") (pintype "passive"))
      (node (ref "IC15") (pin "3") (pinfunction "1IN+_3") (pintype "passive"))
      (node (ref "IC15") (pin "5") (pinfunction "2IN+_5") (pintype "passive"))
      (node (ref "IC16") (pin "3") (pinfunction "1IN+_3") (pintype "passive"))
      (node (ref "IC16") (pin "5") (pinfunction "2IN+_5") (pintype "passive"))
      (node (ref "IC30") (pin "13") (pinfunction "-_13") (pintype "passive"))
      (node (ref "IC30") (pin "4") (pinfunction "-_4") (pintype "passive"))
      (node (ref "IC31") (pin "5") (pinfunction "2IN+_5") (pintype "passive"))
      (node (ref "IC32") (pin "3") (pinfunction "1IN+_3") (pintype "passive"))
      (node (ref "IC32") (pin "5") (pinfunction "2IN+_5") (pintype "passive"))
      (node (ref "J10") (pin "5") (pinfunction "5_5") (pintype "passive"))
      (node (ref "J13") (pin "5") (pinfunction "5_5") (pintype "passive"))
      (node (ref "Q1") (pin "1") (pinfunction "B_1") (pintype "passive"))
      (node (ref "Q2") (pin "1") (pinfunction "B_1") (pintype "passive"))
      (node (ref "Q5") (pin "1") (pinfunction "B_1") (pintype "passive"))
      (node (ref "Q6") (pin "1") (pinfunction "B_1") (pintype "passive"))
      (node (ref "R1") (pin "1") (pinfunction "1_1") (pintype "passive"))
      (node (ref "R12") (pin "1") (pinfunction "1_1") (pintype "passive"))
      (node (ref "R14") (pin "1") (pinfunction "1_1") (pintype "passive"))
      (node (ref "R17") (pin "1") (pinfunction "1_1") (pintype "passive"))
      (node (ref "R19") (pin "1") (pinfunction "1_1") (pintype "passive"))
      (node (ref "R3") (pin "1") (pinfunction "1_1") (pintype "passive"))
      (node (ref "R30") (pin "1") (pinfunction "1_1") (pintype "passive"))
      (node (ref "R32") (pin "1") (pinfunction "1_1") (pintype "passive"))
      (node (ref "R43") (pin "2") (pinfunction "2_2") (pintype "passive"))
      (node (ref "R45") (pin "2") (pinfunction "2_2") (pintype "passive"))
      (node (ref "R53") (pin "2") (pinfunction "2_2") (pintype "passive"))
      (node (ref "R55") (pin "2") (pinfunction "2_2") (pintype "passive"))
    )
    (net (code "26") (name "Net-(C9-Pad1)") (class "Default")
      (node (ref "C9") (pin "1") (pinfunction "1_1") (pintype "passive"))
      (node (ref "R13") (pin "2") (pinfunction "2_2") (pintype "passive"))
    )
    (net (code "27") (name "Net-(C10-Pad1)") (class "Default")
      (node (ref "C10") (pin "1") (pinfunction "1_1") (pintype "passive"))
      (node (ref "R18") (pin "2") (pinfunction "2_2") (pintype "passive"))
    )
    (net (code "28") (name "Net-(IC10A-+)") (class "Default")
      (node (ref "IC10") (pin "3") (pinfunction "+_3") (pintype "passive"))
      (node (ref "R3") (pin "2") (pinfunction "2_2") (pintype "passive"))
      (node (ref "R7") (pin "2") (pinfunction "2_2") (pintype "passive"))
      (node (ref "R9") (pin "1") (pinfunction "1_1") (pintype "passive"))
    )
    (net (code "29") (name "Net-(IC10A-OUT)") (class "Default")
      (node (ref "C6") (pin "2") (pinfunction "2_2") (pintype "passive"))
      (node (ref "IC10") (pin "5") (pinfunction "OUT_5") (pintype "passive"))
      (node (ref "IC11") (pin "6") (pinfunction "2IN-_6") (pintype "passive"))
    )
    (net (code "30") (name "Net-(IC10C-+)") (class "Default")
      (node (ref "IC10") (pin "14") (pinfunction "+_14") (pintype "passive"))
      (node (ref "R1") (pin "2") (pinfunction "2_2") (pintype "passive"))
      (node (ref "R4") (pin "2") (pinfunction "2_2") (pintype "passive"))
      (node (ref "R8") (pin "1") (pinfunction "1_1") (pintype "passive"))
    )
    (net (code "31") (name "Net-(IC10C-OUT)") (class "Default")
      (node (ref "C5") (pin "2") (pinfunction "2_2") (pintype "passive"))
      (node (ref "IC10") (pin "12") (pinfunction "OUT_12") (pintype "passive"))
      (node (ref "IC12") (pin "2") (pinfunction "1IN-_2") (pintype "passive"))
    )
    (net (code "32") (name "Net-(IC11A-1IN+)") (class "Default")
      (node (ref "IC11") (pin "3") (pinfunction "1IN+_3") (pintype "passive"))
      (node (ref "IC20") (pin "5") (pinfunction "OUT_5") (pintype "passive"))
      (node (ref "R6") (pin "2") (pinfunction "2_2") (pintype "passive"))
    )
    (net (code "33") (name "Net-(IC11A-1IN-)") (class "Default")
      (node (ref "IC11") (pin "2") (pinfunction "1IN-_2") (pintype "passive"))
      (node (ref "R10") (pin "1") (pinfunction "1_1") (pintype "passive"))
      (node (ref "R11") (pin "1") (pinfunction "1_1") (pintype "passive"))
    )
    (net (code "34") (name "Net-(IC12A-1OUT)") (class "Default")
      (node (ref "C5") (pin "1") (pinfunction "1_1") (pintype "passive"))
      (node (ref "IC12") (pin "1") (pinfunction "1OUT_1") (pintype "passive"))
      (node (ref "R11") (pin "2") (pinfunction "2_2") (pintype "passive"))
      (node (ref "R2") (pin "1") (pinfunction "1_1") (pintype "passive"))
      (node (ref "R8") (pin "2") (pinfunction "2_2") (pintype "passive"))
    )
    (net (code "35") (name "Net-(IC12B-2IN-)") (class "Default")
      (node (ref "IC12") (pin "6") (pinfunction "2IN-_6") (pintype "passive"))
      (node (ref "R2") (pin "2") (pinfunction "2_2") (pintype "passive"))
      (node (ref "R5") (pin "1") (pinfunction "1_1") (pintype "passive"))
    )
    (net (code "36") (name "Net-(IC15A-1IN-)") (class "Default")
      (node (ref "C1") (pin "2") (pinfunction "2_2") (pintype "passive"))
      (node (ref "IC15") (pin "2") (pinfunction "1IN-_2") (pintype "passive"))
      (node (ref "R42") (pin "1") (pinfunction "1_1") (pintype "passive"))
      (node (ref "R47") (pin "2") (pinfunction "2_2") (pintype "passive"))
    )
    (net (code "37") (name "Net-(IC15A-1OUT)") (class "Default")
      (node (ref "C1") (pin "1") (pinfunction "1_1") (pintype "passive"))
      (node (ref "IC15") (pin "1") (pinfunction "1OUT_1") (pintype "passive"))
      (node (ref "Q3") (pin "1") (pinfunction "B_1") (pintype "passive"))
    )
    (net (code "38") (name "Net-(IC15B-1OUT)") (class "Default")
      (node (ref "C2") (pin "1") (pinfunction "1_1") (pintype "passive"))
      (node (ref "IC15") (pin "7") (pinfunction "1OUT_7") (pintype "passive"))
      (node (ref "Q4") (pin "1") (pinfunction "B_1") (pintype "passive"))
    )
    (net (code "39") (name "Net-(IC15B-2IN-)") (class "Default")
      (node (ref "C2") (pin "2") (pinfunction "2_2") (pintype "passive"))
      (node (ref "IC15") (pin "6") (pinfunction "2IN-_6") (pintype "passive"))
      (node (ref "R44") (pin "1") (pinfunction "1_1") (pintype "passive"))
      (node (ref "R48") (pin "2") (pinfunction "2_2") (pintype "passive"))
    )
    (net (code "40") (name "Net-(IC16A-1IN-)") (class "Default")
      (node (ref "C27") (pin "2") (pinfunction "2_2") (pintype "passive"))
      (node (ref "IC16") (pin "2") (pinfunction "1IN-_2") (pintype "passive"))
      (node (ref "R52") (pin "1") (pinfunction "1_1") (pintype "passive"))
      (node (ref "R58") (pin "2") (pinfunction "2_2") (pintype "passive"))
    )
    (net (code "41") (name "Net-(IC16A-1OUT)") (class "Default")
      (node (ref "C27") (pin "1") (pinfunction "1_1") (pintype "passive"))
      (node (ref "IC16") (pin "1") (pinfunction "1OUT_1") (pintype "passive"))
      (node (ref "Q7") (pin "1") (pinfunction "B_1") (pintype "passive"))
    )
    (net (code "42") (name "Net-(IC16B-1OUT)") (class "Default")
      (node (ref "C28") (pin "1") (pinfunction "1_1") (pintype "passive"))
      (node (ref "IC16") (pin "7") (pinfunction "1OUT_7") (pintype "passive"))
      (node (ref "Q8") (pin "1") (pinfunction "B_1") (pintype "passive"))
    )
    (net (code "43") (name "Net-(IC16B-2IN-)") (class "Default")
      (node (ref "C28") (pin "2") (pinfunction "2_2") (pintype "passive"))
      (node (ref "IC16") (pin "6") (pinfunction "2IN-_6") (pintype "passive"))
      (node (ref "R54") (pin "1") (pinfunction "1_1") (pintype "passive"))
      (node (ref "R59") (pin "2") (pinfunction "2_2") (pintype "passive"))
    )
    (net (code "44") (name "Net-(IC20A-+)") (class "Default")
      (node (ref "IC20") (pin "3") (pinfunction "+_3") (pintype "passive"))
      (node (ref "R12") (pin "2") (pinfunction "2_2") (pintype "passive"))
      (node (ref "R13") (pin "1") (pinfunction "1_1") (pintype "passive"))
    )
    (net (code "45") (name "Net-(IC20A--)") (class "Default")
      (node (ref "IC20") (pin "4") (pinfunction "-_4") (pintype "passive"))
      (node (ref "R14") (pin "2") (pinfunction "2_2") (pintype "passive"))
      (node (ref "R15") (pin "1") (pinfunction "1_1") (pintype "passive"))
    )
    (net (code "46") (name "Net-(IC20C-+)") (class "Default")
      (node (ref "IC20") (pin "14") (pinfunction "+_14") (pintype "passive"))
      (node (ref "R18") (pin "1") (pinfunction "1_1") (pintype "passive"))
      (node (ref "R19") (pin "2") (pinfunction "2_2") (pintype "passive"))
    )
    (net (code "47") (name "Net-(IC20C--)") (class "Default")
      (node (ref "IC20") (pin "13") (pinfunction "-_13") (pintype "passive"))
      (node (ref "R16") (pin "1") (pinfunction "1_1") (pintype "passive"))
      (node (ref "R17") (pin "2") (pinfunction "2_2") (pintype "passive"))
    )
    (net (code "48") (name "Net-(IC20C-OUT)") (class "Default")
      (node (ref "IC20") (pin "12") (pinfunction "OUT_12") (pintype "passive"))
      (node (ref "IC31") (pin "3") (pinfunction "1IN+_3") (pintype "passive"))
      (node (ref "R27") (pin "2") (pinfunction "2_2") (pintype "passive"))
    )
    (net (code "49") (name "Net-(IC30A-+)") (class "Default")
      (node (ref "IC30") (pin "3") (pinfunction "+_3") (pintype "passive"))
      (node (ref "R24") (pin "1") (pinfunction "1_1") (pintype "passive"))
      (node (ref "R26") (pin "2") (pinfunction "2_2") (pintype "passive"))
      (node (ref "R30") (pin "2") (pinfunction "2_2") (pintype "passive"))
    )
    (net (code "50") (name "Net-(IC30A-OUT)") (class "Default")
      (node (ref "C11") (pin "2") (pinfunction "2_2") (pintype "passive"))
      (node (ref "IC30") (pin "5") (pinfunction "OUT_5") (pintype "passive"))
      (node (ref "IC31") (pin "6") (pinfunction "2IN-_6") (pintype "passive"))
    )
    (net (code "51") (name "Net-(IC30C-+)") (class "Default")
      (node (ref "IC30") (pin "14") (pinfunction "+_14") (pintype "passive"))
      (node (ref "R25") (pin "1") (pinfunction "1_1") (pintype "passive"))
      (node (ref "R29") (pin "2") (pinfunction "2_2") (pintype "passive"))
      (node (ref "R32") (pin "2") (pinfunction "2_2") (pintype "passive"))
    )
    (net (code "52") (name "Net-(IC30C-OUT)") (class "Default")
      (node (ref "C12") (pin "2") (pinfunction "2_2") (pintype "passive"))
      (node (ref "IC30") (pin "12") (pinfunction "OUT_12") (pintype "passive"))
      (node (ref "IC32") (pin "2") (pinfunction "1IN-_2") (pintype "passive"))
    )
    (net (code "53") (name "Net-(IC31A-1IN-)") (class "Default")
      (node (ref "IC31") (pin "2") (pinfunction "1IN-_2") (pintype "passive"))
      (node (ref "R20") (pin "1") (pinfunction "1_1") (pintype "passive"))
      (node (ref "R23") (pin "1") (pinfunction "1_1") (pintype "passive"))
    )
    (net (code "54") (name "Net-(IC32A-1OUT)") (class "Default")
      (node (ref "C12") (pin "1") (pinfunction "1_1") (pintype "passive"))
      (node (ref "IC32") (pin "1") (pinfunction "1OUT_1") (pintype "passive"))
      (node (ref "R20") (pin "2") (pinfunction "2_2") (pintype "passive"))
      (node (ref "R25") (pin "2") (pinfunction "2_2") (pintype "passive"))
      (node (ref "R31") (pin "1") (pinfunction "1_1") (pintype "passive"))
    )
    (net (code "55") (name "Net-(IC32B-2IN-)") (class "Default")
      (node (ref "IC32") (pin "6") (pinfunction "2IN-_6") (pintype "passive"))
      (node (ref "R28") (pin "1") (pinfunction "1_1") (pintype "passive"))
      (node (ref "R31") (pin "2") (pinfunction "2_2") (pintype "passive"))
    )
    (net (code "56") (name "Net-(Q1-C)") (class "Default")
      (node (ref "J8") (pin "1") (pinfunction "IN_1") (pintype "passive"))
      (node (ref "Q1") (pin "3") (pinfunction "C_3") (pintype "passive"))
      (node (ref "R42") (pin "2") (pinfunction "2_2") (pintype "passive"))
    )
    (net (code "57") (name "Net-(Q1-E)") (class "Default")
      (node (ref "J8") (pin "2") (pinfunction "IN_2") (pintype "passive"))
      (node (ref "Q1") (pin "2") (pinfunction "E_2") (pintype "passive"))
      (node (ref "Q3") (pin "2") (pinfunction "E_2") (pintype "passive"))
      (node (ref "R43") (pin "1") (pinfunction "1_1") (pintype "passive"))
    )
    (net (code "58") (name "Net-(Q2-C)") (class "Default")
      (node (ref "J9") (pin "1") (pinfunction "IN_1") (pintype "passive"))
      (node (ref "Q2") (pin "3") (pinfunction "C_3") (pintype "passive"))
      (node (ref "R44") (pin "2") (pinfunction "2_2") (pintype "passive"))
    )
    (net (code "59") (name "Net-(Q2-E)") (class "Default")
      (node (ref "J9") (pin "2") (pinfunction "IN_2") (pintype "passive"))
      (node (ref "Q2") (pin "2") (pinfunction "E_2") (pintype "passive"))
      (node (ref "Q4") (pin "2") (pinfunction "E_2") (pintype "passive"))
      (node (ref "R45") (pin "1") (pinfunction "1_1") (pintype "passive"))
    )
    (net (code "60") (name "Net-(Q3-C)") (class "Default")
      (node (ref "Q3") (pin "3") (pinfunction "C_3") (pintype "passive"))
      (node (ref "R49") (pin "2") (pinfunction "2_2") (pintype "passive"))
      (node (ref "R50") (pin "2") (pinfunction "2_2") (pintype "passive"))
    )
    (net (code "61") (name "Net-(Q4-C)") (class "Default")
      (node (ref "Q4") (pin "3") (pinfunction "C_3") (pintype "passive"))
      (node (ref "R51") (pin "2") (pinfunction "2_2") (pintype "passive"))
    )
    (net (code "62") (name "Net-(Q5-C)") (class "Default")
      (node (ref "J11") (pin "1") (pinfunction "IN_1") (pintype "passive"))
      (node (ref "Q5") (pin "3") (pinfunction "C_3") (pintype "passive"))
      (node (ref "R52") (pin "2") (pinfunction "2_2") (pintype "passive"))
    )
    (net (code "63") (name "Net-(Q5-E)") (class "Default")
      (node (ref "J11") (pin "2") (pinfunction "IN_2") (pintype "passive"))
      (node (ref "Q5") (pin "2") (pinfunction "E_2") (pintype "passive"))
      (node (ref "Q7") (pin "2") (pinfunction "E_2") (pintype "passive"))
      (node (ref "R53") (pin "1") (pinfunction "1_1") (pintype "passive"))
    )
    (net (code "64") (name "Net-(Q6-C)") (class "Default")
      (node (ref "J12") (pin "1") (pinfunction "IN_1") (pintype "passive"))
      (node (ref "Q6") (pin "3") (pinfunction "C_3") (pintype "passive"))
      (node (ref "R54") (pin "2") (pinfunction "2_2") (pintype "passive"))
    )
    (net (code "65") (name "Net-(Q6-E)") (class "Default")
      (node (ref "J12") (pin "2") (pinfunction "IN_2") (pintype "passive"))
      (node (ref "Q6") (pin "2") (pinfunction "E_2") (pintype "passive"))
      (node (ref "Q8") (pin "2") (pinfunction "E_2") (pintype "passive"))
      (node (ref "R55") (pin "1") (pinfunction "1_1") (pintype "passive"))
    )
    (net (code "66") (name "Net-(Q7-C)") (class "Default")
      (node (ref "Q7") (pin "3") (pinfunction "C_3") (pintype "passive"))
      (node (ref "R60") (pin "2") (pinfunction "2_2") (pintype "passive"))
      (node (ref "R61") (pin "2") (pinfunction "2_2") (pintype "passive"))
    )
    (net (code "67") (name "Net-(Q8-C)") (class "Default")
      (node (ref "Q8") (pin "3") (pinfunction "C_3") (pintype "passive"))
      (node (ref "R62") (pin "2") (pinfunction "2_2") (pintype "passive"))
    )
    (net (code "68") (name "unconnected-(IC10A-DIODE_BIAS_1-Pad2)") (class "Default")
      (node (ref "IC10") (pin "2") (pinfunction "DIODE_BIAS_1_2") (pintype "passive"))
    )
    (net (code "69") (name "unconnected-(IC10C-DIODE_BIAS_1-Pad15)") (class "Default")
      (node (ref "IC10") (pin "15") (pinfunction "DIODE_BIAS_1_15") (pintype "passive"))
    )
    (net (code "70") (name "unconnected-(IC20A-DIODE_BIAS_1-Pad2)") (class "Default")
      (node (ref "IC20") (pin "2") (pinfunction "DIODE_BIAS_1_2") (pintype "passive"))
    )
    (net (code "71") (name "unconnected-(IC20C-DIODE_BIAS_1-Pad15)") (class "Default")
      (node (ref "IC20") (pin "15") (pinfunction "DIODE_BIAS_1_15") (pintype "passive"))
    )
    (net (code "72") (name "unconnected-(IC30A-DIODE_BIAS_1-Pad2)") (class "Default")
      (node (ref "IC30") (pin "2") (pinfunction "DIODE_BIAS_1_2") (pintype "passive"))
    )
    (net (code "73") (name "unconnected-(IC30C-DIODE_BIAS_1-Pad15)") (class "Default")
      (node (ref "IC30") (pin "15") (pinfunction "DIODE_BIAS_1_15") (pintype "passive"))
    )
  )
)
